# Sheet4.net
KiCad netlist of a schematic drawn in Altium Designer
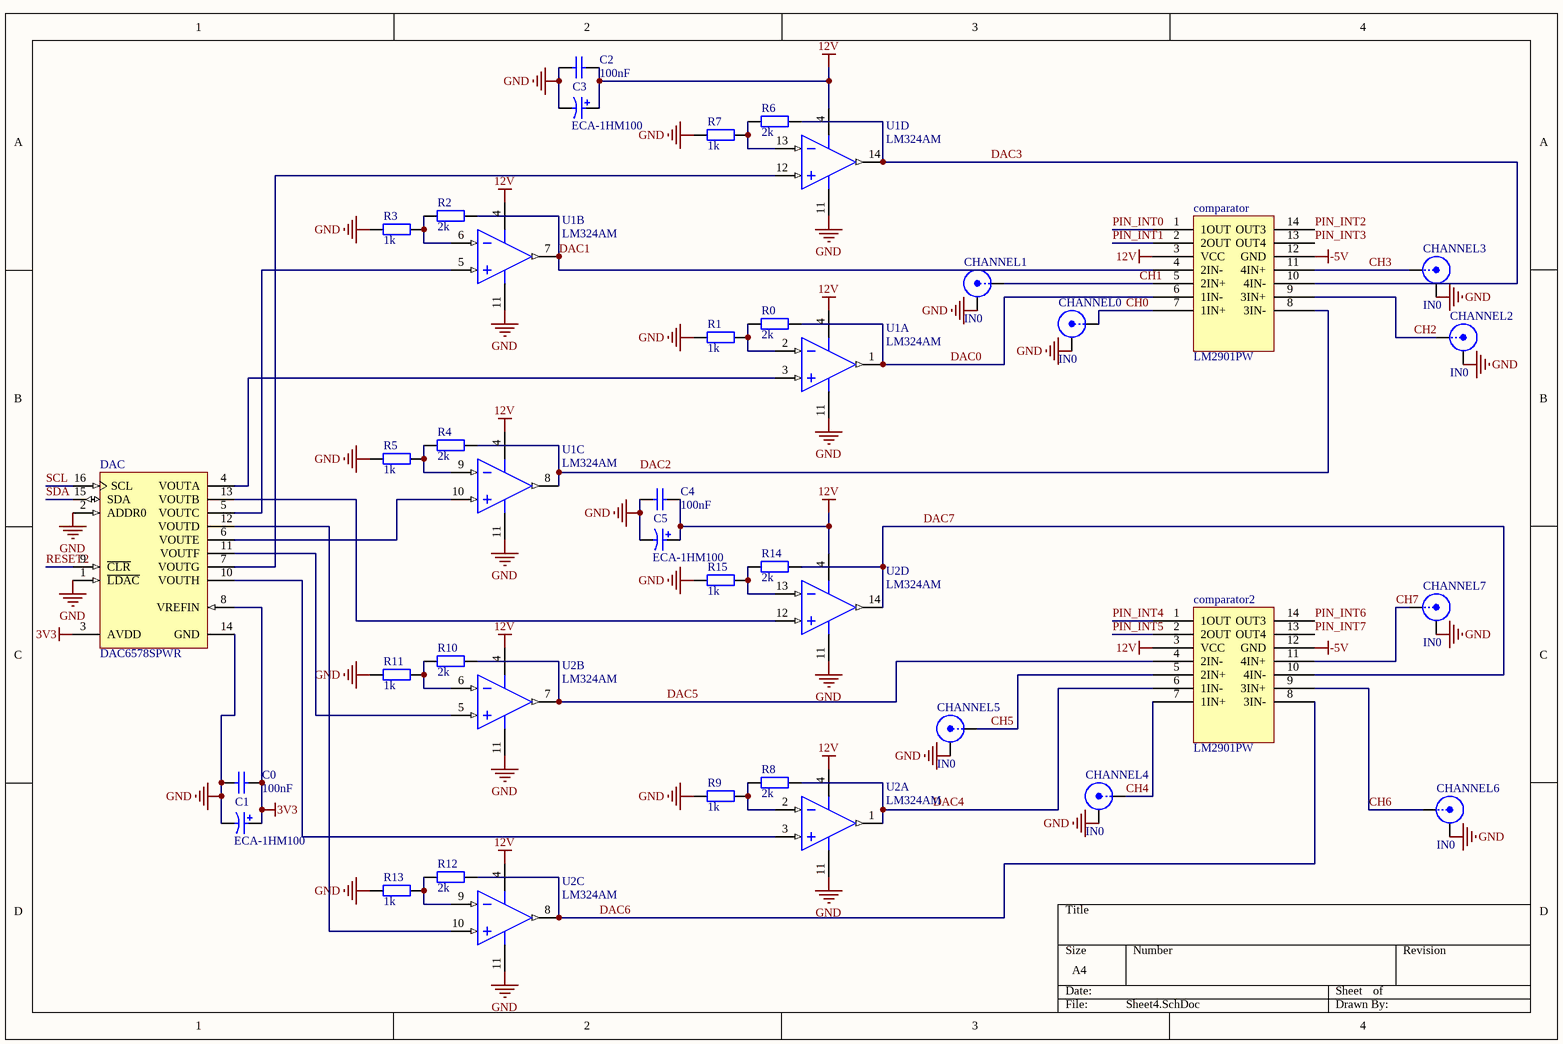
[diagram p0: Sheet4.SchDoc]

(export (version "E")
  (design (tool "Eeschema 10.0.6"))
  (components
    (comp (ref "C0")
      (value "100nF")
      (footprint "C0805")
      (description "Capacitor Cer 50V 0805 Vishay X7R")
      (libsource (lib "capacitors") (part "Ceramic 100nF/50V"))
    )
    (comp (ref "C1")
      (value "ECA-1HM100")
      (footprint "CAPPR55-200-1100X500X1200")
      (description "Aluminum Electrolytic Capacitor, 10 uF, +/- 20%, 50 V, -40 to 85 degC, 2-Pin THD, RoHS, Bulk")
      (libsource (lib "Altium Content Vault") (part "CMP-1665-00038-1"))
    )
    (comp (ref "C2")
      (value "100nF")
      (footprint "C0805")
      (description "Capacitor Cer 50V 0805 Vishay X7R")
      (libsource (lib "capacitors") (part "Ceramic 100nF/50V"))
    )
    (comp (ref "C3")
      (value "ECA-1HM100")
      (footprint "CAPPR55-200-1100X500X1200")
      (description "Aluminum Electrolytic Capacitor, 10 uF, +/- 20%, 50 V, -40 to 85 degC, 2-Pin THD, RoHS, Bulk")
      (libsource (lib "Altium Content Vault") (part "CMP-1665-00038-1"))
    )
    (comp (ref "C4")
      (value "100nF")
      (footprint "C0805")
      (description "Capacitor Cer 50V 0805 Vishay X7R")
      (libsource (lib "capacitors") (part "Ceramic 100nF/50V"))
    )
    (comp (ref "C5")
      (value "ECA-1HM100")
      (footprint "CAPPR55-200-1100X500X1200")
      (description "Aluminum Electrolytic Capacitor, 10 uF, +/- 20%, 50 V, -40 to 85 degC, 2-Pin THD, RoHS, Bulk")
      (libsource (lib "Altium Content Vault") (part "CMP-1665-00038-1"))
    )
    (comp (ref "CHANNEL0")
      (value "IN0")
      (footprint "connectors:SMB")
      (description "SMB Straight Connector")
      (fields (field (name "PUBLISHER") "Altium Limited"))
      (libsource (lib "connectors") (part "SMB"))
    )
    (comp (ref "CHANNEL1")
      (value "IN0")
      (footprint "connectors:SMB")
      (description "SMB Straight Connector")
      (fields (field (name "PUBLISHER") "Altium Limited"))
      (libsource (lib "connectors") (part "SMB"))
    )
    (comp (ref "CHANNEL2")
      (value "IN0")
      (footprint "connectors:SMB")
      (description "SMB Straight Connector")
      (fields (field (name "PUBLISHER") "Altium Limited"))
      (libsource (lib "connectors") (part "SMB"))
    )
    (comp (ref "CHANNEL3")
      (value "IN0")
      (footprint "connectors:SMB")
      (description "SMB Straight Connector")
      (fields (field (name "PUBLISHER") "Altium Limited"))
      (libsource (lib "connectors") (part "SMB"))
    )
    (comp (ref "CHANNEL4")
      (value "IN0")
      (footprint "connectors:SMB")
      (description "SMB Straight Connector")
      (fields (field (name "PUBLISHER") "Altium Limited"))
      (libsource (lib "connectors") (part "SMB"))
    )
    (comp (ref "CHANNEL5")
      (value "IN0")
      (footprint "connectors:SMB")
      (description "SMB Straight Connector")
      (fields (field (name "PUBLISHER") "Altium Limited"))
      (libsource (lib "connectors") (part "SMB"))
    )
    (comp (ref "CHANNEL6")
      (value "IN0")
      (footprint "connectors:SMB")
      (description "SMB Straight Connector")
      (fields (field (name "PUBLISHER") "Altium Limited"))
      (libsource (lib "connectors") (part "SMB"))
    )
    (comp (ref "CHANNEL7")
      (value "IN0")
      (footprint "connectors:SMB")
      (description "SMB Straight Connector")
      (fields (field (name "PUBLISHER") "Altium Limited"))
      (libsource (lib "connectors") (part "SMB"))
    )
    (comp (ref "comparator")
      (value "LM2901PW")
      (footprint "TSSOP-14")
      (libsource (lib "schlib") (part "LM2901PW"))
    )
    (comp (ref "comparator2")
      (value "LM2901PW")
      (footprint "TSSOP-14")
      (libsource (lib "schlib") (part "LM2901PW"))
    )
    (comp (ref "DAC")
      (value "DAC6578SPWR")
      (footprint "TI-PW16_N")
      (fields (field (name "MANUFACTURER") "Texas Instruments"))
      (libsource (lib "Altium Content Vault") (part "CMP-0004-01130-1"))
    )
    (comp (ref "R0")
      (value "2k")
      (footprint "6-0805_N")
      (description "Resistor")
      (fields (field (name "Comment") "2k-0W25-0805") (field (name "PUBLISHER") "Altium Limited"))
      (libsource (lib "resistors_0805") (part "1k-0W25-0805"))
    )
    (comp (ref "R1")
      (value "1k")
      (footprint "6-0805_N")
      (description "Resistor")
      (fields (field (name "Comment") "1k-0W25-0805") (field (name "PUBLISHER") "Altium Limited"))
      (libsource (lib "resistors_0805") (part "1k-0W25-0805"))
    )
    (comp (ref "R2")
      (value "2k")
      (footprint "6-0805_N")
      (description "Resistor")
      (fields (field (name "Comment") "2k-0W25-0805") (field (name "PUBLISHER") "Altium Limited"))
      (libsource (lib "resistors_0805") (part "1k-0W25-0805"))
    )
    (comp (ref "R3")
      (value "1k")
      (footprint "6-0805_N")
      (description "Resistor")
      (fields (field (name "Comment") "1k-0W25-0805") (field (name "PUBLISHER") "Altium Limited"))
      (libsource (lib "resistors_0805") (part "1k-0W25-0805"))
    )
    (comp (ref "R4")
      (value "2k")
      (footprint "6-0805_N")
      (description "Resistor")
      (fields (field (name "Comment") "2k-0W25-0805") (field (name "PUBLISHER") "Altium Limited"))
      (libsource (lib "resistors_0805") (part "1k-0W25-0805"))
    )
    (comp (ref "R5")
      (value "1k")
      (footprint "6-0805_N")
      (description "Resistor")
      (fields (field (name "Comment") "1k-0W25-0805") (field (name "PUBLISHER") "Altium Limited"))
      (libsource (lib "resistors_0805") (part "1k-0W25-0805"))
    )
    (comp (ref "R6")
      (value "2k")
      (footprint "6-0805_N")
      (description "Resistor")
      (fields (field (name "Comment") "2k-0W25-0805") (field (name "PUBLISHER") "Altium Limited"))
      (libsource (lib "resistors_0805") (part "1k-0W25-0805"))
    )
    (comp (ref "R7")
      (value "1k")
      (footprint "6-0805_N")
      (description "Resistor")
      (fields (field (name "Comment") "1k-0W25-0805") (field (name "PUBLISHER") "Altium Limited"))
      (libsource (lib "resistors_0805") (part "1k-0W25-0805"))
    )
    (comp (ref "R8")
      (value "2k")
      (footprint "6-0805_N")
      (description "Resistor")
      (fields (field (name "Comment") "2k-0W25-0805") (field (name "PUBLISHER") "Altium Limited"))
      (libsource (lib "resistors_0805") (part "1k-0W25-0805"))
    )
    (comp (ref "R9")
      (value "1k")
      (footprint "6-0805_N")
      (description "Resistor")
      (fields (field (name "Comment") "1k-0W25-0805") (field (name "PUBLISHER") "Altium Limited"))
      (libsource (lib "resistors_0805") (part "1k-0W25-0805"))
    )
    (comp (ref "R10")
      (value "2k")
      (footprint "6-0805_N")
      (description "Resistor")
      (fields (field (name "Comment") "2k-0W25-0805") (field (name "PUBLISHER") "Altium Limited"))
      (libsource (lib "resistors_0805") (part "1k-0W25-0805"))
    )
    (comp (ref "R11")
      (value "1k")
      (footprint "6-0805_N")
      (description "Resistor")
      (fields (field (name "Comment") "1k-0W25-0805") (field (name "PUBLISHER") "Altium Limited"))
      (libsource (lib "resistors_0805") (part "1k-0W25-0805"))
    )
    (comp (ref "R12")
      (value "2k")
      (footprint "6-0805_N")
      (description "Resistor")
      (fields (field (name "Comment") "2k-0W25-0805") (field (name "PUBLISHER") "Altium Limited"))
      (libsource (lib "resistors_0805") (part "1k-0W25-0805"))
    )
    (comp (ref "R13")
      (value "1k")
      (footprint "6-0805_N")
      (description "Resistor")
      (fields (field (name "Comment") "1k-0W25-0805") (field (name "PUBLISHER") "Altium Limited"))
      (libsource (lib "resistors_0805") (part "1k-0W25-0805"))
    )
    (comp (ref "R14")
      (value "2k")
      (footprint "6-0805_N")
      (description "Resistor")
      (fields (field (name "Comment") "2k-0W25-0805") (field (name "PUBLISHER") "Altium Limited"))
      (libsource (lib "resistors_0805") (part "1k-0W25-0805"))
    )
    (comp (ref "R15")
      (value "1k")
      (footprint "6-0805_N")
      (description "Resistor")
      (fields (field (name "Comment") "1k-0W25-0805") (field (name "PUBLISHER") "Altium Limited"))
      (libsource (lib "resistors_0805") (part "1k-0W25-0805"))
    )
    (comp (ref "U1")
      (value "LM324AM")
      (footprint "D0014A_N")
      (description "Low Power Quad Operational Amplifier, 14-pin Narrow SOIC")
      (fields (field (name "MANUFACTURER") "Texas Instruments"))
      (libsource (lib "Altium Content Vault") (part "CMP-0055-00794-3"))
    )
    (comp (ref "U2")
      (value "LM324AM")
      (footprint "D0014A_N")
      (description "Low Power Quad Operational Amplifier, 14-pin Narrow SOIC")
      (fields (field (name "MANUFACTURER") "Texas Instruments"))
      (libsource (lib "Altium Content Vault") (part "CMP-0055-00794-3"))
    )
  )
  (nets
    (net (code "1") (name "-5V") (class "Default")
      (node (ref "comparator") (pin "12") (pinfunction "GND_12") (pintype "passive"))
      (node (ref "comparator2") (pin "12") (pinfunction "GND_12") (pintype "passive"))
    )
    (net (code "2") (name "/CH0") (class "Default")
      (node (ref "CHANNEL0") (pin "1") (pinfunction "X_1") (pintype "passive"))
      (node (ref "comparator") (pin "7") (pinfunction "1IN+_7") (pintype "passive"))
    )
    (net (code "3") (name "/CH1") (class "Default")
      (node (ref "CHANNEL1") (pin "1") (pinfunction "X_1") (pintype "passive"))
      (node (ref "comparator") (pin "5") (pinfunction "2IN+_5") (pintype "passive"))
    )
    (net (code "4") (name "/CH2") (class "Default")
      (node (ref "CHANNEL2") (pin "1") (pinfunction "X_1") (pintype "passive"))
      (node (ref "comparator") (pin "9") (pinfunction "3IN+_9") (pintype "passive"))
    )
    (net (code "5") (name "/CH3") (class "Default")
      (node (ref "CHANNEL3") (pin "1") (pinfunction "X_1") (pintype "passive"))
      (node (ref "comparator") (pin "11") (pinfunction "4IN+_11") (pintype "passive"))
    )
    (net (code "6") (name "/CH4") (class "Default")
      (node (ref "CHANNEL4") (pin "1") (pinfunction "X_1") (pintype "passive"))
      (node (ref "comparator2") (pin "7") (pinfunction "1IN+_7") (pintype "passive"))
    )
    (net (code "7") (name "/CH5") (class "Default")
      (node (ref "CHANNEL5") (pin "1") (pinfunction "X_1") (pintype "passive"))
      (node (ref "comparator2") (pin "5") (pinfunction "2IN+_5") (pintype "passive"))
    )
    (net (code "8") (name "/CH6") (class "Default")
      (node (ref "CHANNEL6") (pin "1") (pinfunction "X_1") (pintype "passive"))
      (node (ref "comparator2") (pin "9") (pinfunction "3IN+_9") (pintype "passive"))
    )
    (net (code "9") (name "/CH7") (class "Default")
      (node (ref "CHANNEL7") (pin "1") (pinfunction "X_1") (pintype "passive"))
      (node (ref "comparator2") (pin "11") (pinfunction "4IN+_11") (pintype "passive"))
    )
    (net (code "10") (name "/DAC0") (class "Default")
      (node (ref "R0") (pin "2") (pinfunction "2_2") (pintype "passive"))
      (node (ref "U1") (pin "1") (pinfunction "OUT1_1") (pintype "output"))
      (node (ref "comparator") (pin "6") (pinfunction "1IN-_6") (pintype "passive"))
    )
    (net (code "11") (name "/DAC1") (class "Default")
      (node (ref "R2") (pin "2") (pinfunction "2_2") (pintype "passive"))
      (node (ref "U1") (pin "7") (pinfunction "OUT2_7") (pintype "output"))
      (node (ref "comparator") (pin "4") (pinfunction "2IN-_4") (pintype "passive"))
    )
    (net (code "12") (name "/DAC2") (class "Default")
      (node (ref "R4") (pin "2") (pinfunction "2_2") (pintype "passive"))
      (node (ref "U1") (pin "8") (pinfunction "OUT3_8") (pintype "output"))
      (node (ref "comparator") (pin "8") (pinfunction "3IN-_8") (pintype "passive"))
    )
    (net (code "13") (name "/DAC3") (class "Default")
      (node (ref "R6") (pin "2") (pinfunction "2_2") (pintype "passive"))
      (node (ref "U1") (pin "14") (pinfunction "OUT4_14") (pintype "output"))
      (node (ref "comparator") (pin "10") (pinfunction "4IN-_10") (pintype "passive"))
    )
    (net (code "14") (name "/DAC4") (class "Default")
      (node (ref "R8") (pin "2") (pinfunction "2_2") (pintype "passive"))
      (node (ref "U2") (pin "1") (pinfunction "OUT1_1") (pintype "output"))
      (node (ref "comparator2") (pin "6") (pinfunction "1IN-_6") (pintype "passive"))
    )
    (net (code "15") (name "/DAC5") (class "Default")
      (node (ref "R10") (pin "2") (pinfunction "2_2") (pintype "passive"))
      (node (ref "U2") (pin "7") (pinfunction "OUT2_7") (pintype "output"))
      (node (ref "comparator2") (pin "4") (pinfunction "2IN-_4") (pintype "passive"))
    )
    (net (code "16") (name "/DAC6") (class "Default")
      (node (ref "R12") (pin "2") (pinfunction "2_2") (pintype "passive"))
      (node (ref "U2") (pin "8") (pinfunction "OUT3_8") (pintype "output"))
      (node (ref "comparator2") (pin "8") (pinfunction "3IN-_8") (pintype "passive"))
    )
    (net (code "17") (name "/DAC7") (class "Default")
      (node (ref "R14") (pin "2") (pinfunction "2_2") (pintype "passive"))
      (node (ref "U2") (pin "14") (pinfunction "OUT4_14") (pintype "output"))
      (node (ref "comparator2") (pin "10") (pinfunction "4IN-_10") (pintype "passive"))
    )
    (net (code "18") (name "/PIN_INT0") (class "Default")
      (node (ref "comparator") (pin "1") (pinfunction "1OUT_1") (pintype "passive"))
    )
    (net (code "19") (name "/PIN_INT1") (class "Default")
      (node (ref "comparator") (pin "2") (pinfunction "2OUT_2") (pintype "passive"))
    )
    (net (code "20") (name "/PIN_INT2") (class "Default")
      (node (ref "comparator") (pin "14") (pinfunction "OUT3_14") (pintype "passive"))
    )
    (net (code "21") (name "/PIN_INT3") (class "Default")
      (node (ref "comparator") (pin "13") (pinfunction "OUT4_13") (pintype "passive"))
    )
    (net (code "22") (name "/PIN_INT4") (class "Default")
      (node (ref "comparator2") (pin "1") (pinfunction "1OUT_1") (pintype "passive"))
    )
    (net (code "23") (name "/PIN_INT5") (class "Default")
      (node (ref "comparator2") (pin "2") (pinfunction "2OUT_2") (pintype "passive"))
    )
    (net (code "24") (name "/PIN_INT6") (class "Default")
      (node (ref "comparator2") (pin "14") (pinfunction "OUT3_14") (pintype "passive"))
    )
    (net (code "25") (name "/PIN_INT7") (class "Default")
      (node (ref "comparator2") (pin "13") (pinfunction "OUT4_13") (pintype "passive"))
    )
    (net (code "26") (name "/RESET2") (class "Default")
      (node (ref "DAC") (pin "9") (pinfunction "~{CLR}_9") (pintype "input"))
    )
    (net (code "27") (name "/SCL") (class "Default")
      (node (ref "DAC") (pin "16") (pinfunction "SCL_16") (pintype "input"))
    )
    (net (code "28") (name "/SDA") (class "Default")
      (node (ref "DAC") (pin "15") (pinfunction "SDA_15") (pintype "bidirectional"))
    )
    (net (code "29") (name "3V3") (class "Default")
      (node (ref "C0") (pin "2") (pinfunction "2_2") (pintype "passive"))
      (node (ref "C1") (pin "1") (pinfunction "1_1") (pintype "passive"))
      (node (ref "DAC") (pin "3") (pinfunction "AVDD_3") (pintype "power_in"))
      (node (ref "DAC") (pin "8") (pinfunction "VREFIN_8") (pintype "input"))
    )
    (net (code "30") (name "12V") (class "Default")
      (node (ref "C2") (pin "2") (pinfunction "2_2") (pintype "passive"))
      (node (ref "C3") (pin "1") (pinfunction "1_1") (pintype "passive"))
      (node (ref "C4") (pin "2") (pinfunction "2_2") (pintype "passive"))
      (node (ref "C5") (pin "1") (pinfunction "1_1") (pintype "passive"))
      (node (ref "U1") (pin "4") (pinfunction "V+_4") (pintype "power_in"))
      (node (ref "U2") (pin "4") (pinfunction "V+_4") (pintype "power_in"))
      (node (ref "comparator") (pin "3") (pinfunction "VCC_3") (pintype "passive"))
      (node (ref "comparator2") (pin "3") (pinfunction "VCC_3") (pintype "passive"))
    )
    (net (code "31") (name "GND") (class "Default")
      (node (ref "C0") (pin "1") (pinfunction "1_1") (pintype "passive"))
      (node (ref "C1") (pin "2") (pinfunction "2_2") (pintype "passive"))
      (node (ref "C2") (pin "1") (pinfunction "1_1") (pintype "passive"))
      (node (ref "C3") (pin "2") (pinfunction "2_2") (pintype "passive"))
      (node (ref "C4") (pin "1") (pinfunction "1_1") (pintype "passive"))
      (node (ref "C5") (pin "2") (pinfunction "2_2") (pintype "passive"))
      (node (ref "CHANNEL0") (pin "2") (pinfunction "Y_2") (pintype "passive"))
      (node (ref "CHANNEL1") (pin "2") (pinfunction "Y_2") (pintype "passive"))
      (node (ref "CHANNEL2") (pin "2") (pinfunction "Y_2") (pintype "passive"))
      (node (ref "CHANNEL3") (pin "2") (pinfunction "Y_2") (pintype "passive"))
      (node (ref "CHANNEL4") (pin "2") (pinfunction "Y_2") (pintype "passive"))
      (node (ref "CHANNEL5") (pin "2") (pinfunction "Y_2") (pintype "passive"))
      (node (ref "CHANNEL6") (pin "2") (pinfunction "Y_2") (pintype "passive"))
      (node (ref "CHANNEL7") (pin "2") (pinfunction "Y_2") (pintype "passive"))
      (node (ref "DAC") (pin "1") (pinfunction "~{LDAC}_1") (pintype "input"))
      (node (ref "DAC") (pin "14") (pinfunction "GND_14") (pintype "power_in"))
      (node (ref "DAC") (pin "2") (pinfunction "ADDR0_2") (pintype "input"))
      (node (ref "R1") (pin "1") (pinfunction "1_1") (pintype "passive"))
      (node (ref "R11") (pin "1") (pinfunction "1_1") (pintype "passive"))
      (node (ref "R13") (pin "1") (pinfunction "1_1") (pintype "passive"))
      (node (ref "R15") (pin "1") (pinfunction "1_1") (pintype "passive"))
      (node (ref "R3") (pin "1") (pinfunction "1_1") (pintype "passive"))
      (node (ref "R5") (pin "1") (pinfunction "1_1") (pintype "passive"))
      (node (ref "R7") (pin "1") (pinfunction "1_1") (pintype "passive"))
      (node (ref "R9") (pin "1") (pinfunction "1_1") (pintype "passive"))
      (node (ref "U1") (pin "11") (pinfunction "GND_11") (pintype "power_in"))
      (node (ref "U2") (pin "11") (pinfunction "GND_11") (pintype "power_in"))
    )
    (net (code "32") (name "Net-(DAC-VOUTA)") (class "Default")
      (node (ref "DAC") (pin "4") (pinfunction "VOUTA_4") (pintype "tri_state"))
      (node (ref "U1") (pin "3") (pinfunction "IN1+_3") (pintype "input"))
    )
    (net (code "33") (name "Net-(DAC-VOUTB)") (class "Default")
      (node (ref "DAC") (pin "13") (pinfunction "VOUTB_13") (pintype "tri_state"))
      (node (ref "U2") (pin "12") (pinfunction "IN4+_12") (pintype "input"))
    )
    (net (code "34") (name "Net-(DAC-VOUTC)") (class "Default")
      (node (ref "DAC") (pin "5") (pinfunction "VOUTC_5") (pintype "tri_state"))
      (node (ref "U1") (pin "5") (pinfunction "IN2+_5") (pintype "input"))
    )
    (net (code "35") (name "Net-(DAC-VOUTD)") (class "Default")
      (node (ref "DAC") (pin "12") (pinfunction "VOUTD_12") (pintype "tri_state"))
      (node (ref "U2") (pin "10") (pinfunction "IN3+_10") (pintype "input"))
    )
    (net (code "36") (name "Net-(DAC-VOUTE)") (class "Default")
      (node (ref "DAC") (pin "6") (pinfunction "VOUTE_6") (pintype "tri_state"))
      (node (ref "U1") (pin "10") (pinfunction "IN3+_10") (pintype "input"))
    )
    (net (code "37") (name "Net-(DAC-VOUTF)") (class "Default")
      (node (ref "DAC") (pin "11") (pinfunction "VOUTF_11") (pintype "tri_state"))
      (node (ref "U2") (pin "5") (pinfunction "IN2+_5") (pintype "input"))
    )
    (net (code "38") (name "Net-(DAC-VOUTG)") (class "Default")
      (node (ref "DAC") (pin "7") (pinfunction "VOUTG_7") (pintype "tri_state"))
      (node (ref "U1") (pin "12") (pinfunction "IN4+_12") (pintype "input"))
    )
    (net (code "39") (name "Net-(DAC-VOUTH)") (class "Default")
      (node (ref "DAC") (pin "10") (pinfunction "VOUTH_10") (pintype "tri_state"))
      (node (ref "U2") (pin "3") (pinfunction "IN1+_3") (pintype "input"))
    )
    (net (code "40") (name "Net-(U1A-IN1-)") (class "Default")
      (node (ref "R0") (pin "1") (pinfunction "1_1") (pintype "passive"))
      (node (ref "R1") (pin "2") (pinfunction "2_2") (pintype "passive"))
      (node (ref "U1") (pin "2") (pinfunction "IN1-_2") (pintype "input"))
    )
    (net (code "41") (name "Net-(U1B-IN2-)") (class "Default")
      (node (ref "R2") (pin "1") (pinfunction "1_1") (pintype "passive"))
      (node (ref "R3") (pin "2") (pinfunction "2_2") (pintype "passive"))
      (node (ref "U1") (pin "6") (pinfunction "IN2-_6") (pintype "input"))
    )
    (net (code "42") (name "Net-(U1C-IN3-)") (class "Default")
      (node (ref "R4") (pin "1") (pinfunction "1_1") (pintype "passive"))
      (node (ref "R5") (pin "2") (pinfunction "2_2") (pintype "passive"))
      (node (ref "U1") (pin "9") (pinfunction "IN3-_9") (pintype "input"))
    )
    (net (code "43") (name "Net-(U1D-IN4-)") (class "Default")
      (node (ref "R6") (pin "1") (pinfunction "1_1") (pintype "passive"))
      (node (ref "R7") (pin "2") (pinfunction "2_2") (pintype "passive"))
      (node (ref "U1") (pin "13") (pinfunction "IN4-_13") (pintype "input"))
    )
    (net (code "44") (name "Net-(U2A-IN1-)") (class "Default")
      (node (ref "R8") (pin "1") (pinfunction "1_1") (pintype "passive"))
      (node (ref "R9") (pin "2") (pinfunction "2_2") (pintype "passive"))
      (node (ref "U2") (pin "2") (pinfunction "IN1-_2") (pintype "input"))
    )
    (net (code "45") (name "Net-(U2B-IN2-)") (class "Default")
      (node (ref "R10") (pin "1") (pinfunction "1_1") (pintype "passive"))
      (node (ref "R11") (pin "2") (pinfunction "2_2") (pintype "passive"))
      (node (ref "U2") (pin "6") (pinfunction "IN2-_6") (pintype "input"))
    )
    (net (code "46") (name "Net-(U2C-IN3-)") (class "Default")
      (node (ref "R12") (pin "1") (pinfunction "1_1") (pintype "passive"))
      (node (ref "R13") (pin "2") (pinfunction "2_2") (pintype "passive"))
      (node (ref "U2") (pin "9") (pinfunction "IN3-_9") (pintype "input"))
    )
    (net (code "47") (name "Net-(U2D-IN4-)") (class "Default")
      (node (ref "R14") (pin "1") (pinfunction "1_1") (pintype "passive"))
      (node (ref "R15") (pin "2") (pinfunction "2_2") (pintype "passive"))
      (node (ref "U2") (pin "13") (pinfunction "IN4-_13") (pintype "input"))
    )
  )
)
